# TPS7A9101DSKT.net
KiCad netlist of a schematic drawn in Altium Designer
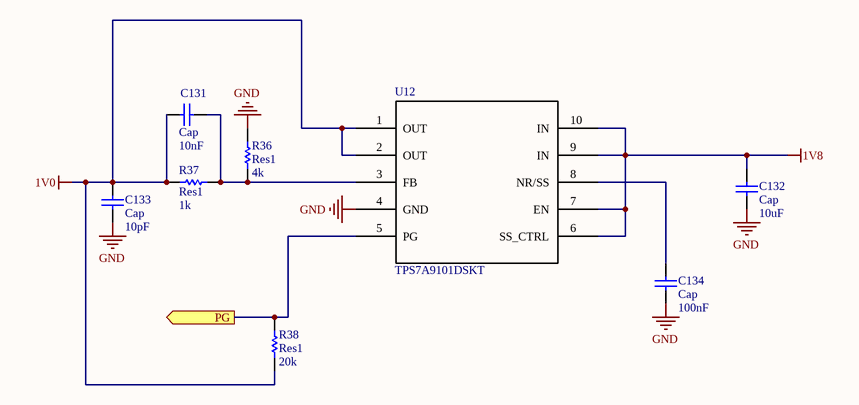
[diagram p0: TPS7A9101DSKT.SchDoc]

(export (version "E")
  (design (tool "Eeschema 10.0.6"))
  (components
    (comp (ref "C131")
      (value "Cap")
      (footprint "0402-A")
      (description "Capacitor")
      (fields (field (name "ALTIUM_VALUE") "10nF") (field (name "PUBLISHER") "Altium Limited"))
      (libsource (lib "Miscellaneous Devices") (part "Cap"))
    )
    (comp (ref "C132")
      (value "Cap")
      (footprint "C1206")
      (description "Capacitor")
      (fields (field (name "ALTIUM_VALUE") "10uF") (field (name "PUBLISHER") "Altium Limited"))
      (libsource (lib "Miscellaneous Devices") (part "Cap"))
    )
    (comp (ref "C133")
      (value "Cap")
      (footprint "0402-A")
      (description "Capacitor")
      (fields (field (name "ALTIUM_VALUE") "10pF") (field (name "PUBLISHER") "Altium Limited"))
      (libsource (lib "Miscellaneous Devices") (part "Cap"))
    )
    (comp (ref "C134")
      (value "Cap")
      (footprint "0402-A")
      (description "Capacitor")
      (fields (field (name "ALTIUM_VALUE") "100nF") (field (name "PUBLISHER") "Altium Limited"))
      (libsource (lib "Miscellaneous Devices") (part "Cap"))
    )
    (comp (ref "R36")
      (value "Res1")
      (footprint "0402-A")
      (description "Resistor")
      (fields (field (name "ALTIUM_VALUE") "4k") (field (name "PUBLISHER") "Altium Limited"))
      (libsource (lib "Miscellaneous Devices") (part "Res1"))
    )
    (comp (ref "R37")
      (value "Res1")
      (footprint "0402-A")
      (description "Resistor")
      (fields (field (name "ALTIUM_VALUE") "1k") (field (name "PUBLISHER") "Altium Limited"))
      (libsource (lib "Miscellaneous Devices") (part "Res1"))
    )
    (comp (ref "R38")
      (value "Res1")
      (footprint "0402-A")
      (description "Resistor")
      (fields (field (name "ALTIUM_VALUE") "20k") (field (name "PUBLISHER") "Altium Limited"))
      (libsource (lib "Miscellaneous Devices") (part "Res1"))
    )
    (comp (ref "U12")
      (value "TPS7A9101DSKT")
      (footprint "TPS7A9101DSKT")
      (libsource (lib "TPS7A9101DSKT") (part "TPS7A9101DSKT"))
    )
  )
  (nets
    (net (code "1") (name "/PG") (class "Default")
      (node (ref "R38") (pin "2") (pinfunction "2_2") (pintype "passive"))
      (node (ref "U12") (pin "5") (pinfunction "PG_5") (pintype "passive"))
    )
    (net (code "2") (name "1V0") (class "Default")
      (node (ref "C131") (pin "1") (pinfunction "1_1") (pintype "passive"))
      (node (ref "C133") (pin "1") (pinfunction "1_1") (pintype "passive"))
      (node (ref "R37") (pin "1") (pinfunction "1_1") (pintype "passive"))
      (node (ref "R38") (pin "1") (pinfunction "1_1") (pintype "passive"))
      (node (ref "U12") (pin "1") (pinfunction "OUT_1") (pintype "passive"))
      (node (ref "U12") (pin "2") (pinfunction "OUT_2") (pintype "passive"))
    )
    (net (code "3") (name "1V8") (class "Default")
      (node (ref "C132") (pin "2") (pinfunction "2_2") (pintype "passive"))
      (node (ref "U12") (pin "10") (pinfunction "IN_10") (pintype "passive"))
      (node (ref "U12") (pin "6") (pinfunction "SS_CTRL_6") (pintype "passive"))
      (node (ref "U12") (pin "7") (pinfunction "EN_7") (pintype "passive"))
      (node (ref "U12") (pin "9") (pinfunction "IN_9") (pintype "passive"))
    )
    (net (code "4") (name "GND") (class "Default")
      (node (ref "C132") (pin "1") (pinfunction "1_1") (pintype "passive"))
      (node (ref "C133") (pin "2") (pinfunction "2_2") (pintype "passive"))
      (node (ref "C134") (pin "1") (pinfunction "1_1") (pintype "passive"))
      (node (ref "R36") (pin "2") (pinfunction "2_2") (pintype "passive"))
      (node (ref "U12") (pin "4") (pinfunction "GND_4") (pintype "passive"))
    )
    (net (code "5") (name "Net-(U12-FB)") (class "Default")
      (node (ref "C131") (pin "2") (pinfunction "2_2") (pintype "passive"))
      (node (ref "R36") (pin "1") (pinfunction "1_1") (pintype "passive"))
      (node (ref "R37") (pin "2") (pinfunction "2_2") (pintype "passive"))
      (node (ref "U12") (pin "3") (pinfunction "FB_3") (pintype "passive"))
    )
    (net (code "6") (name "Net-(U12-NR{slash}SS)") (class "Default")
      (node (ref "C134") (pin "2") (pinfunction "2_2") (pintype "passive"))
      (node (ref "U12") (pin "8") (pinfunction "NR/SS_8") (pintype "passive"))
    )
  )
)
